# level-shifter-v1_0.net
KiCad netlist of a schematic drawn in EAGLE
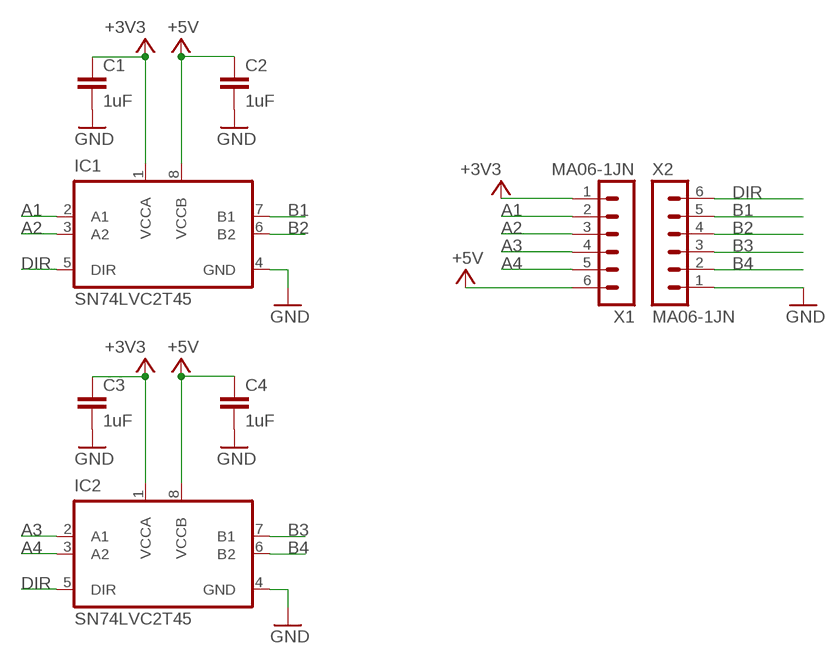
[diagram p0: schematic, sheet 1]

(export (version "E")
  (design (tool "Eeschema 10.0.6"))
  (components
    (comp (ref "C1")
      (value "1uF")
      (footprint "eagle-import:C0402-J")
      (libsource (lib "eagle-import") (part "C-EU-J0402"))
    )
    (comp (ref "C2")
      (value "1uF")
      (footprint "eagle-import:C0402-J")
      (libsource (lib "eagle-import") (part "C-EU-J0402"))
    )
    (comp (ref "C3")
      (value "1uF")
      (footprint "eagle-import:C0402-J")
      (libsource (lib "eagle-import") (part "C-EU-J0402"))
    )
    (comp (ref "C4")
      (value "1uF")
      (footprint "eagle-import:C0402-J")
      (libsource (lib "eagle-import") (part "C-EU-J0402"))
    )
    (comp (ref "IC1")
      (value "SN74LVC2T45")
      (footprint "eagle-import:VSSOP8J")
      (libsource (lib "eagle-import") (part "SN74LVC2T45"))
    )
    (comp (ref "IC2")
      (value "SN74LVC2T45")
      (footprint "eagle-import:VSSOP8J")
      (libsource (lib "eagle-import") (part "SN74LVC2T45"))
    )
    (comp (ref "X1")
      (value "MA06-1JN")
      (footprint "eagle-import:MA06N-1J")
      (libsource (lib "eagle-import") (part "MA06-1JN"))
    )
    (comp (ref "X2")
      (value "MA06-1JN")
      (footprint "eagle-import:MA06N-1J")
      (libsource (lib "eagle-import") (part "MA06-1JN"))
    )
  )
  (nets
    (net (code "1") (name "+3V3") (class "Default")
      (node (ref "C1") (pin "1") (pinfunction "1_1") (pintype "passive"))
      (node (ref "C3") (pin "1") (pinfunction "1_1") (pintype "passive"))
      (node (ref "IC1") (pin "1") (pinfunction "VCCA_1") (pintype "power_in"))
      (node (ref "IC2") (pin "1") (pinfunction "VCCA_1") (pintype "power_in"))
      (node (ref "X1") (pin "1") (pinfunction "1_1") (pintype "passive"))
    )
    (net (code "2") (name "+5V") (class "Default")
      (node (ref "C2") (pin "1") (pinfunction "1_1") (pintype "passive"))
      (node (ref "C4") (pin "1") (pinfunction "1_1") (pintype "passive"))
      (node (ref "IC1") (pin "8") (pinfunction "VCCB_8") (pintype "power_in"))
      (node (ref "IC2") (pin "8") (pinfunction "VCCB_8") (pintype "power_in"))
      (node (ref "X1") (pin "6") (pinfunction "6_6") (pintype "passive"))
    )
    (net (code "3") (name "/A1") (class "Default")
      (node (ref "IC1") (pin "2") (pinfunction "A1_2") (pintype "bidirectional"))
      (node (ref "X1") (pin "2") (pinfunction "2_2") (pintype "passive"))
    )
    (net (code "4") (name "/A2") (class "Default")
      (node (ref "IC1") (pin "3") (pinfunction "A2_3") (pintype "bidirectional"))
      (node (ref "X1") (pin "3") (pinfunction "3_3") (pintype "passive"))
    )
    (net (code "5") (name "/A3") (class "Default")
      (node (ref "IC2") (pin "2") (pinfunction "A1_2") (pintype "bidirectional"))
      (node (ref "X1") (pin "4") (pinfunction "4_4") (pintype "passive"))
    )
    (net (code "6") (name "/A4") (class "Default")
      (node (ref "IC2") (pin "3") (pinfunction "A2_3") (pintype "bidirectional"))
      (node (ref "X1") (pin "5") (pinfunction "5_5") (pintype "passive"))
    )
    (net (code "7") (name "/B1") (class "Default")
      (node (ref "IC1") (pin "7") (pinfunction "B1_7") (pintype "bidirectional"))
      (node (ref "X2") (pin "5") (pinfunction "5_5") (pintype "passive"))
    )
    (net (code "8") (name "/B2") (class "Default")
      (node (ref "IC1") (pin "6") (pinfunction "B2_6") (pintype "bidirectional"))
      (node (ref "X2") (pin "4") (pinfunction "4_4") (pintype "passive"))
    )
    (net (code "9") (name "/B3") (class "Default")
      (node (ref "IC2") (pin "7") (pinfunction "B1_7") (pintype "bidirectional"))
      (node (ref "X2") (pin "3") (pinfunction "3_3") (pintype "passive"))
    )
    (net (code "10") (name "/B4") (class "Default")
      (node (ref "IC2") (pin "6") (pinfunction "B2_6") (pintype "bidirectional"))
      (node (ref "X2") (pin "2") (pinfunction "2_2") (pintype "passive"))
    )
    (net (code "11") (name "/DIR") (class "Default")
      (node (ref "IC1") (pin "5") (pinfunction "DIR_5") (pintype "bidirectional"))
      (node (ref "IC2") (pin "5") (pinfunction "DIR_5") (pintype "bidirectional"))
      (node (ref "X2") (pin "6") (pinfunction "6_6") (pintype "passive"))
    )
    (net (code "12") (name "GND") (class "Default")
      (node (ref "C1") (pin "2") (pinfunction "2_2") (pintype "passive"))
      (node (ref "C2") (pin "2") (pinfunction "2_2") (pintype "passive"))
      (node (ref "C3") (pin "2") (pinfunction "2_2") (pintype "passive"))
      (node (ref "C4") (pin "2") (pinfunction "2_2") (pintype "passive"))
      (node (ref "IC1") (pin "4") (pinfunction "GND_4") (pintype "power_in"))
      (node (ref "IC2") (pin "4") (pinfunction "GND_4") (pintype "power_in"))
      (node (ref "X2") (pin "1") (pinfunction "1_1") (pintype "passive"))
    )
  )
)
